# ad_test_sch1.net
KiCad netlist of a schematic drawn in Altium Designer
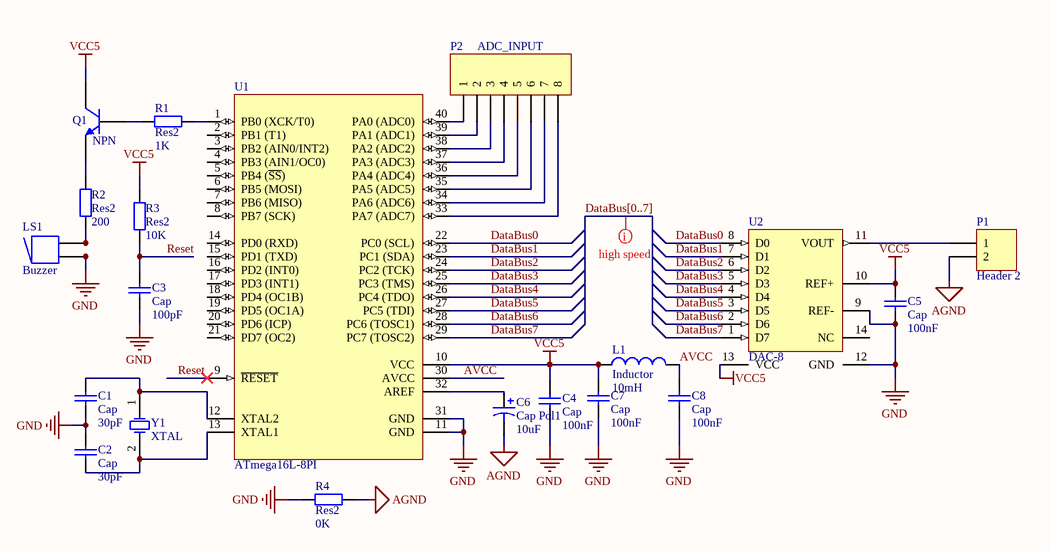
[diagram p0: ad_test_sch1.SchDoc]

(export (version "E")
  (design (tool "Eeschema 10.0.6"))
  (components
    (comp (ref "C1")
      (value "Cap")
      (footprint "RAD-0.3")
      (description "Capacitor")
      (fields (field (name "ALTIUM_VALUE") "30pF") (field (name "PUBLISHER") "Altium Limited"))
      (libsource (lib "Miscellaneous Devices") (part "Cap"))
    )
    (comp (ref "C2")
      (value "Cap")
      (footprint "RAD-0.3")
      (description "Capacitor")
      (fields (field (name "ALTIUM_VALUE") "30pF") (field (name "PUBLISHER") "Altium Limited"))
      (libsource (lib "Miscellaneous Devices") (part "Cap"))
    )
    (comp (ref "C3")
      (value "Cap")
      (footprint "RAD-0.3")
      (description "Capacitor")
      (fields (field (name "ALTIUM_VALUE") "100pF") (field (name "PUBLISHER") "Altium Limited"))
      (libsource (lib "Miscellaneous Devices") (part "Cap"))
    )
    (comp (ref "C4")
      (value "Cap")
      (footprint "RAD-0.3")
      (description "Capacitor")
      (fields (field (name "ALTIUM_VALUE") "100nF") (field (name "PUBLISHER") "Altium Limited"))
      (libsource (lib "Miscellaneous Devices") (part "Cap"))
    )
    (comp (ref "C5")
      (value "Cap")
      (footprint "RAD-0.3")
      (description "Capacitor")
      (fields (field (name "ALTIUM_VALUE") "100nF") (field (name "PUBLISHER") "Altium Limited"))
      (libsource (lib "Miscellaneous Devices") (part "Cap"))
    )
    (comp (ref "C6")
      (value "Cap Pol1")
      (footprint "RB7.6-15")
      (description "Polarized Capacitor (Radial)")
      (fields (field (name "ALTIUM_VALUE") "10uF") (field (name "PUBLISHER") "Altium Limited"))
      (libsource (lib "Miscellaneous Devices") (part "Cap Pol1"))
    )
    (comp (ref "C7")
      (value "Cap")
      (footprint "RAD-0.3")
      (description "Capacitor")
      (fields (field (name "ALTIUM_VALUE") "100nF") (field (name "PUBLISHER") "Altium Limited"))
      (libsource (lib "Miscellaneous Devices") (part "Cap"))
    )
    (comp (ref "C8")
      (value "Cap")
      (footprint "RAD-0.3")
      (description "Capacitor")
      (fields (field (name "ALTIUM_VALUE") "100nF") (field (name "PUBLISHER") "Altium Limited"))
      (libsource (lib "Miscellaneous Devices") (part "Cap"))
    )
    (comp (ref "L1")
      (value "Inductor")
      (footprint "INDC1608L")
      (fields (field (name "ALTIUM_VALUE") "10mH") (field (name "PUBLISHER") "Altium Limited"))
      (libsource (lib "Miscellaneous Devices") (part "Inductor"))
    )
    (comp (ref "LS1")
      (value "Buzzer")
      (footprint "ABSM-1574")
      (description "Magnetic Transducer Buzzer")
      (fields (field (name "PUBLISHER") "Altium Limited"))
      (libsource (lib "Miscellaneous Devices") (part "Buzzer"))
    )
    (comp (ref "P1")
      (value "Header 2")
      (footprint "HDR1X2")
      (description "Header, 2-Pin")
      (fields (field (name "PUBLISHER") "Altium Limited"))
      (libsource (lib "Miscellaneous Connectors") (part "Header 2"))
    )
    (comp (ref "P2")
      (value "ADC_INPUT")
      (footprint "HDR1X8H")
      (description "Header, 8-Pin, Right Angle")
      (fields (field (name "PUBLISHER") "Altium Limited"))
      (libsource (lib "Miscellaneous Connectors") (part "Header 8H"))
    )
    (comp (ref "Q1")
      (value "NPN")
      (footprint "TO-226-AA")
      (description "NPN Bipolar Transistor")
      (fields (field (name "PUBLISHER") "Altium Limited"))
      (libsource (lib "Miscellaneous Devices") (part "NPN"))
    )
    (comp (ref "R1")
      (value "Res2")
      (footprint "AXIAL-0.4")
      (description "Resistor")
      (fields (field (name "ALTIUM_VALUE") "1K") (field (name "PUBLISHER") "Altium Limited"))
      (libsource (lib "") (part "Res2_1"))
    )
    (comp (ref "R2")
      (value "Res2")
      (footprint "AXIAL-0.4")
      (description "Resistor")
      (fields (field (name "ALTIUM_VALUE") "200") (field (name "PUBLISHER") "Altium Limited"))
      (libsource (lib "Miscellaneous Devices") (part "Res2"))
    )
    (comp (ref "R3")
      (value "Res2")
      (footprint "AXIAL-0.4")
      (description "Resistor")
      (fields (field (name "ALTIUM_VALUE") "10K") (field (name "PUBLISHER") "Altium Limited"))
      (libsource (lib "Miscellaneous Devices") (part "Res2"))
    )
    (comp (ref "R4")
      (value "Res2")
      (footprint "AXIAL-0.4")
      (description "Resistor")
      (fields (field (name "ALTIUM_VALUE") "0K") (field (name "PUBLISHER") "Altium Limited"))
      (libsource (lib "") (part "Res2_2"))
    )
    (comp (ref "U1")
      (value "ATmega16L-8PI")
      (footprint "40P6")
      (description "8-Bit AVR Microcontroller with 16K Bytes of In-System Programmable Flash Memory")
      (fields (field (name "PUBLISHER") "Altium Limited"))
      (libsource (lib "Atmel Microcontroller 8-Bit AVR") (part "ATmega16L-8PI"))
    )
    (comp (ref "U2")
      (value "DAC-8")
      (footprint "SOT402-1_N")
      (description "Generic 8-Bit D/A Converter")
      (fields (field (name "PUBLISHER") "Altium Limited"))
      (libsource (lib "Miscellaneous Devices") (part "DAC-8"))
    )
    (comp (ref "Y1")
      (value "XTAL")
      (footprint "R38")
      (description "Crystal Oscillator")
      (fields (field (name "PUBLISHER") "Altium Limited"))
      (libsource (lib "Miscellaneous Devices") (part "XTAL"))
    )
  )
  (nets
    (net (code "1") (name "/AVCC") (class "Default")
      (node (ref "C8") (pin "1") (pinfunction "1_1") (pintype "passive"))
      (node (ref "L1") (pin "2") (pinfunction "2_2") (pintype "passive"))
      (node (ref "U1") (pin "30") (pinfunction "AVCC_30") (pintype "power_in"))
    )
    (net (code "2") (name "/DataBus0") (class "Default")
      (node (ref "U1") (pin "22") (pinfunction "PC0_(SCL)_22") (pintype "bidirectional"))
      (node (ref "U2") (pin "8") (pinfunction "D0_8") (pintype "input"))
    )
    (net (code "3") (name "/DataBus1") (class "Default")
      (node (ref "U1") (pin "23") (pinfunction "PC1_(SDA)_23") (pintype "bidirectional"))
      (node (ref "U2") (pin "7") (pinfunction "D1_7") (pintype "input"))
    )
    (net (code "4") (name "/DataBus2") (class "Default")
      (node (ref "U1") (pin "24") (pinfunction "PC2_(TCK)_24") (pintype "bidirectional"))
      (node (ref "U2") (pin "6") (pinfunction "D2_6") (pintype "input"))
    )
    (net (code "5") (name "/DataBus3") (class "Default")
      (node (ref "U1") (pin "25") (pinfunction "PC3_(TMS)_25") (pintype "bidirectional"))
      (node (ref "U2") (pin "5") (pinfunction "D3_5") (pintype "input"))
    )
    (net (code "6") (name "/DataBus4") (class "Default")
      (node (ref "U1") (pin "26") (pinfunction "PC4_(TDO)_26") (pintype "bidirectional"))
      (node (ref "U2") (pin "4") (pinfunction "D4_4") (pintype "input"))
    )
    (net (code "7") (name "/DataBus5") (class "Default")
      (node (ref "U1") (pin "27") (pinfunction "PC5_(TDI)_27") (pintype "bidirectional"))
      (node (ref "U2") (pin "3") (pinfunction "D5_3") (pintype "input"))
    )
    (net (code "8") (name "/DataBus6") (class "Default")
      (node (ref "U1") (pin "28") (pinfunction "PC6_(TOSC1)_28") (pintype "bidirectional"))
      (node (ref "U2") (pin "2") (pinfunction "D6_2") (pintype "input"))
    )
    (net (code "9") (name "/DataBus7") (class "Default")
      (node (ref "U1") (pin "29") (pinfunction "PC7_(TOSC2)_29") (pintype "bidirectional"))
      (node (ref "U2") (pin "1") (pinfunction "D7_1") (pintype "input"))
    )
    (net (code "11") (name "/Reset") (class "Default")
      (node (ref "C3") (pin "2") (pinfunction "2_2") (pintype "passive"))
      (node (ref "R3") (pin "1") (pinfunction "1_1") (pintype "passive"))
      (node (ref "U1") (pin "9") (pinfunction "~{RESET}_9") (pintype "input"))
    )
    (net (code "12") (name "AGND") (class "Default")
      (node (ref "C6") (pin "2") (pinfunction "2_2") (pintype "passive"))
      (node (ref "P1") (pin "2") (pinfunction "2_2") (pintype "passive"))
      (node (ref "R4") (pin "2") (pinfunction "2_2") (pintype "passive"))
    )
    (net (code "13") (name "GND") (class "Default")
      (node (ref "C1") (pin "1") (pinfunction "1_1") (pintype "passive"))
      (node (ref "C2") (pin "2") (pinfunction "2_2") (pintype "passive"))
      (node (ref "C3") (pin "1") (pinfunction "1_1") (pintype "passive"))
      (node (ref "C4") (pin "2") (pinfunction "2_2") (pintype "passive"))
      (node (ref "C5") (pin "2") (pinfunction "2_2") (pintype "passive"))
      (node (ref "C7") (pin "2") (pinfunction "2_2") (pintype "passive"))
      (node (ref "C8") (pin "2") (pinfunction "2_2") (pintype "passive"))
      (node (ref "LS1") (pin "1") (pinfunction "1_1") (pintype "passive"))
      (node (ref "LS1") (pin "1A") (pinfunction "1A_1A") (pintype "passive"))
      (node (ref "R4") (pin "1") (pinfunction "1_1") (pintype "passive"))
      (node (ref "U1") (pin "11") (pinfunction "GND_11") (pintype "power_in"))
      (node (ref "U1") (pin "31") (pinfunction "GND_31") (pintype "power_in"))
      (node (ref "U2") (pin "12") (pinfunction "GND_12") (pintype "power_in"))
      (node (ref "U2") (pin "9") (pinfunction "REF-_9") (pintype "passive"))
    )
    (net (code "14") (name "Net-(LS1-Pad2)") (class "Default")
      (node (ref "LS1") (pin "2") (pinfunction "2_2") (pintype "passive"))
      (node (ref "LS1") (pin "2A") (pinfunction "2A_2A") (pintype "passive"))
      (node (ref "R2") (pin "1") (pinfunction "1_1") (pintype "passive"))
    )
    (net (code "15") (name "Net-(Q1-B)") (class "Default")
      (node (ref "Q1") (pin "2") (pinfunction "B_2") (pintype "passive"))
      (node (ref "R1") (pin "2") (pinfunction "2_2") (pintype "passive"))
    )
    (net (code "16") (name "Net-(Q1-E)") (class "Default")
      (node (ref "Q1") (pin "3") (pinfunction "E_3") (pintype "passive"))
      (node (ref "R2") (pin "2") (pinfunction "2_2") (pintype "passive"))
    )
    (net (code "17") (name "Net-(U1-AREF)") (class "Default")
      (node (ref "C6") (pin "1") (pinfunction "1_1") (pintype "passive"))
      (node (ref "U1") (pin "32") (pinfunction "AREF_32") (pintype "passive"))
    )
    (net (code "18") (name "Net-(U1-PA0_(ADC0))") (class "Default")
      (node (ref "P2") (pin "1") (pinfunction "1_1") (pintype "passive"))
      (node (ref "U1") (pin "40") (pinfunction "PA0_(ADC0)_40") (pintype "bidirectional"))
    )
    (net (code "19") (name "Net-(U1-PA1_(ADC1))") (class "Default")
      (node (ref "P2") (pin "2") (pinfunction "2_2") (pintype "passive"))
      (node (ref "U1") (pin "39") (pinfunction "PA1_(ADC1)_39") (pintype "bidirectional"))
    )
    (net (code "20") (name "Net-(U1-PA2_(ADC2))") (class "Default")
      (node (ref "P2") (pin "3") (pinfunction "3_3") (pintype "passive"))
      (node (ref "U1") (pin "38") (pinfunction "PA2_(ADC2)_38") (pintype "bidirectional"))
    )
    (net (code "21") (name "Net-(U1-PA3_(ADC3))") (class "Default")
      (node (ref "P2") (pin "4") (pinfunction "4_4") (pintype "passive"))
      (node (ref "U1") (pin "37") (pinfunction "PA3_(ADC3)_37") (pintype "bidirectional"))
    )
    (net (code "22") (name "Net-(U1-PA4_(ADC4))") (class "Default")
      (node (ref "P2") (pin "5") (pinfunction "5_5") (pintype "passive"))
      (node (ref "U1") (pin "36") (pinfunction "PA4_(ADC4)_36") (pintype "bidirectional"))
    )
    (net (code "23") (name "Net-(U1-PA5_(ADC5))") (class "Default")
      (node (ref "P2") (pin "6") (pinfunction "6_6") (pintype "passive"))
      (node (ref "U1") (pin "35") (pinfunction "PA5_(ADC5)_35") (pintype "bidirectional"))
    )
    (net (code "24") (name "Net-(U1-PA6_(ADC6))") (class "Default")
      (node (ref "P2") (pin "7") (pinfunction "7_7") (pintype "passive"))
      (node (ref "U1") (pin "34") (pinfunction "PA6_(ADC6)_34") (pintype "bidirectional"))
    )
    (net (code "25") (name "Net-(U1-PA7_(ADC7))") (class "Default")
      (node (ref "P2") (pin "8") (pinfunction "8_8") (pintype "passive"))
      (node (ref "U1") (pin "33") (pinfunction "PA7_(ADC7)_33") (pintype "bidirectional"))
    )
    (net (code "26") (name "Net-(U1-PB0_(XCK{slash}T0))") (class "Default")
      (node (ref "R1") (pin "1") (pinfunction "1_1") (pintype "passive"))
      (node (ref "U1") (pin "1") (pinfunction "PB0_(XCK/T0)_1") (pintype "bidirectional"))
    )
    (net (code "27") (name "Net-(U1-XTAL1)") (class "Default")
      (node (ref "C2") (pin "1") (pinfunction "1_1") (pintype "passive"))
      (node (ref "U1") (pin "13") (pinfunction "XTAL1_13") (pintype "passive"))
      (node (ref "Y1") (pin "2") (pinfunction "OSC2_2") (pintype "passive"))
    )
    (net (code "28") (name "Net-(U1-XTAL2)") (class "Default")
      (node (ref "C1") (pin "2") (pinfunction "2_2") (pintype "passive"))
      (node (ref "U1") (pin "12") (pinfunction "XTAL2_12") (pintype "passive"))
      (node (ref "Y1") (pin "1") (pinfunction "OSC1_1") (pintype "passive"))
    )
    (net (code "29") (name "Net-(U2-VOUT)") (class "Default")
      (node (ref "P1") (pin "1") (pinfunction "1_1") (pintype "passive"))
      (node (ref "U2") (pin "11") (pinfunction "VOUT_11") (pintype "output"))
    )
    (net (code "30") (name "VCC5") (class "Default")
      (node (ref "C4") (pin "1") (pinfunction "1_1") (pintype "passive"))
      (node (ref "C5") (pin "1") (pinfunction "1_1") (pintype "passive"))
      (node (ref "C7") (pin "1") (pinfunction "1_1") (pintype "passive"))
      (node (ref "L1") (pin "1") (pinfunction "1_1") (pintype "passive"))
      (node (ref "Q1") (pin "1") (pinfunction "C_1") (pintype "passive"))
      (node (ref "R3") (pin "2") (pinfunction "2_2") (pintype "passive"))
      (node (ref "U1") (pin "10") (pinfunction "VCC_10") (pintype "power_in"))
      (node (ref "U2") (pin "10") (pinfunction "REF+_10") (pintype "passive"))
      (node (ref "U2") (pin "13") (pinfunction "VCC_13") (pintype "power_in"))
    )
    (net (code "31") (name "unconnected-(U1-PB1_(T1)-Pad2)") (class "Default")
      (node (ref "U1") (pin "2") (pinfunction "PB1_(T1)_2") (pintype "bidirectional"))
    )
    (net (code "32") (name "unconnected-(U1-PB2_(AIN0{slash}INT2)-Pad3)") (class "Default")
      (node (ref "U1") (pin "3") (pinfunction "PB2_(AIN0/INT2)_3") (pintype "bidirectional"))
    )
    (net (code "33") (name "unconnected-(U1-PB3_(AIN1{slash}OC0)-Pad4)") (class "Default")
      (node (ref "U1") (pin "4") (pinfunction "PB3_(AIN1/OC0)_4") (pintype "bidirectional"))
    )
    (net (code "34") (name "unconnected-(U1-PB4_(~{SS})-Pad5)") (class "Default")
      (node (ref "U1") (pin "5") (pinfunction "PB4_(~{SS})_5") (pintype "bidirectional"))
    )
    (net (code "35") (name "unconnected-(U1-PB5_(MOSI)-Pad6)") (class "Default")
      (node (ref "U1") (pin "6") (pinfunction "PB5_(MOSI)_6") (pintype "bidirectional"))
    )
    (net (code "36") (name "unconnected-(U1-PB6_(MISO)-Pad7)") (class "Default")
      (node (ref "U1") (pin "7") (pinfunction "PB6_(MISO)_7") (pintype "bidirectional"))
    )
    (net (code "37") (name "unconnected-(U1-PB7_(SCK)-Pad8)") (class "Default")
      (node (ref "U1") (pin "8") (pinfunction "PB7_(SCK)_8") (pintype "bidirectional"))
    )
    (net (code "38") (name "unconnected-(U1-PD0_(RXD)-Pad14)") (class "Default")
      (node (ref "U1") (pin "14") (pinfunction "PD0_(RXD)_14") (pintype "bidirectional"))
    )
    (net (code "39") (name "unconnected-(U1-PD1_(TXD)-Pad15)") (class "Default")
      (node (ref "U1") (pin "15") (pinfunction "PD1_(TXD)_15") (pintype "bidirectional"))
    )
    (net (code "40") (name "unconnected-(U1-PD2_(INT0)-Pad16)") (class "Default")
      (node (ref "U1") (pin "16") (pinfunction "PD2_(INT0)_16") (pintype "bidirectional"))
    )
    (net (code "41") (name "unconnected-(U1-PD3_(INT1)-Pad17)") (class "Default")
      (node (ref "U1") (pin "17") (pinfunction "PD3_(INT1)_17") (pintype "bidirectional"))
    )
    (net (code "42") (name "unconnected-(U1-PD4_(OC1B)-Pad18)") (class "Default")
      (node (ref "U1") (pin "18") (pinfunction "PD4_(OC1B)_18") (pintype "bidirectional"))
    )
    (net (code "43") (name "unconnected-(U1-PD5_(OC1A)-Pad19)") (class "Default")
      (node (ref "U1") (pin "19") (pinfunction "PD5_(OC1A)_19") (pintype "bidirectional"))
    )
    (net (code "44") (name "unconnected-(U1-PD6_(ICP)-Pad20)") (class "Default")
      (node (ref "U1") (pin "20") (pinfunction "PD6_(ICP)_20") (pintype "bidirectional"))
    )
    (net (code "45") (name "unconnected-(U1-PD7_(OC2)-Pad21)") (class "Default")
      (node (ref "U1") (pin "21") (pinfunction "PD7_(OC2)_21") (pintype "bidirectional"))
    )
    (net (code "46") (name "unconnected-(U2-NC-Pad14)") (class "Default")
      (node (ref "U2") (pin "14") (pinfunction "NC_14") (pintype "passive"))
    )
  )
)
